# cosv-carrier-teensy40.net
KiCad netlist of a schematic drawn in EAGLE
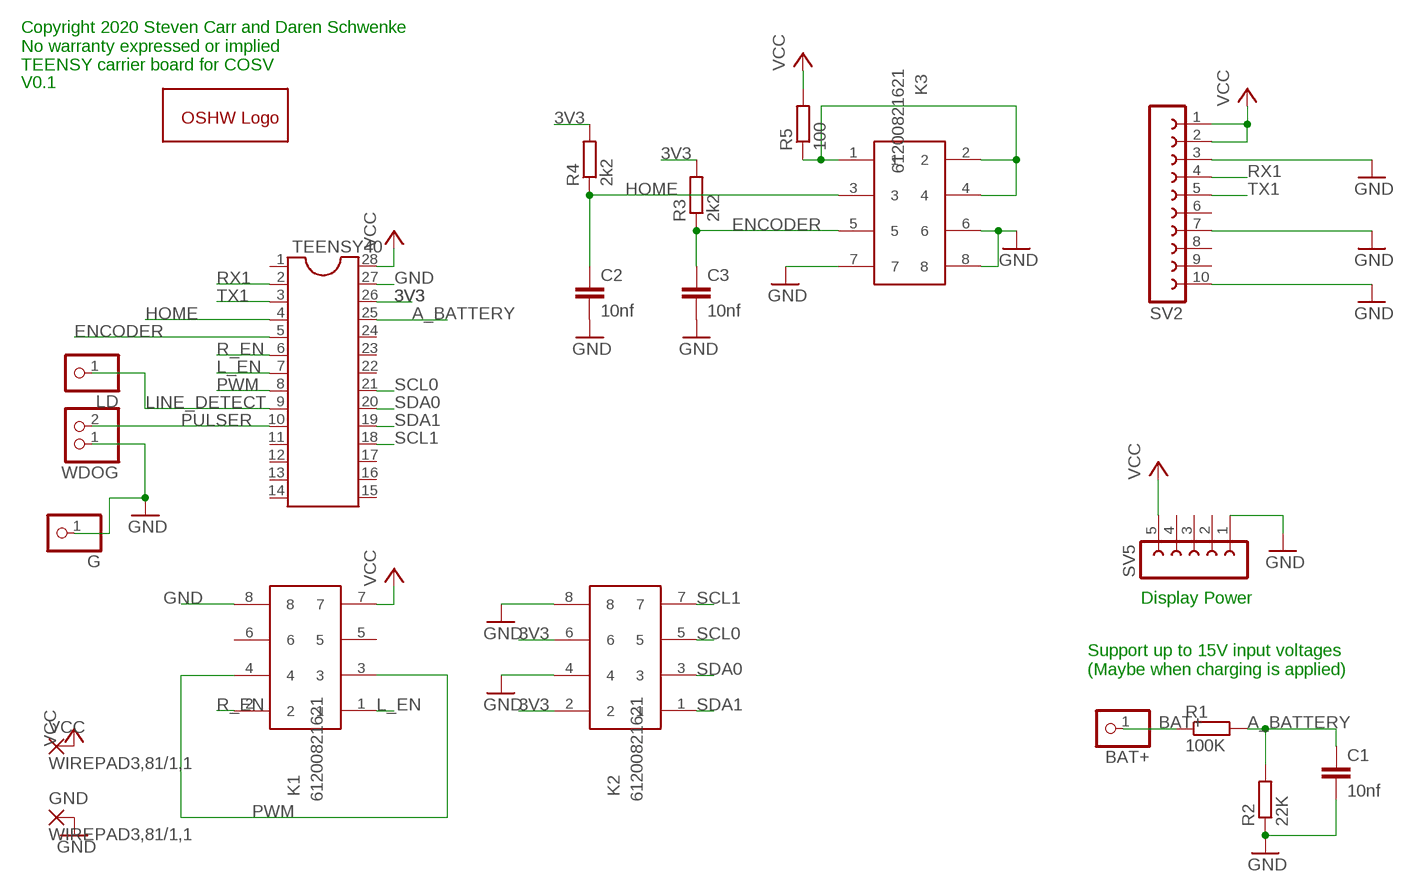
[diagram p0: schematic, sheet 1]

(export (version "E")
  (design (tool "Eeschema 10.0.6"))
  (components
    (comp (ref "BAT+")
      (value "PINHD-1X01_2.54-S")
      (footprint "eagle-import:1X01-S")
      (libsource (lib "eagle-import") (part "PINHD-1X01_2.54-S"))
    )
    (comp (ref "C1")
      (value "10nf")
      (footprint "eagle-import:C1206")
      (libsource (lib "eagle-import") (part "C-EUC1206"))
    )
    (comp (ref "C2")
      (value "10nf")
      (footprint "eagle-import:C1206")
      (libsource (lib "eagle-import") (part "C-EUC1206"))
    )
    (comp (ref "C3")
      (value "10nf")
      (footprint "eagle-import:C1206")
      (libsource (lib "eagle-import") (part "C-EUC1206"))
    )
    (comp (ref "G")
      (value "PINHD-1X01_2.54-S")
      (footprint "eagle-import:1X01-S")
      (libsource (lib "eagle-import") (part "PINHD-1X01_2.54-S"))
    )
    (comp (ref "GND")
      (value "WIREPAD3,81/1,1")
      (footprint "eagle-import:3,81_1,1")
      (libsource (lib "eagle-import") (part "WIREPAD3,81/1,1"))
    )
    (comp (ref "GOLD_ORB_SM1")
      (value "OSHWLOGOLOGO8MM")
      (footprint "eagle-import:OSHW_8MM")
      (libsource (lib "eagle-import") (part "OSHWLOGOLOGO8MM"))
    )
    (comp (ref "K1")
      (value "61200821621")
      (footprint "eagle-import:61200821621")
      (libsource (lib "eagle-import") (part "61200821621"))
    )
    (comp (ref "K2")
      (value "61200821621")
      (footprint "eagle-import:61200821621")
      (libsource (lib "eagle-import") (part "61200821621"))
    )
    (comp (ref "K3")
      (value "61200821621")
      (footprint "eagle-import:61200821621")
      (libsource (lib "eagle-import") (part "61200821621"))
    )
    (comp (ref "LD")
      (value "PINHD-1X01_2.54-S")
      (footprint "eagle-import:1X01-S")
      (libsource (lib "eagle-import") (part "PINHD-1X01_2.54-S"))
    )
    (comp (ref "R1")
      (value "100K")
      (footprint "eagle-import:R1206")
      (libsource (lib "eagle-import") (part "R-EU_R1206"))
    )
    (comp (ref "R2")
      (value "22K")
      (footprint "eagle-import:R1206")
      (libsource (lib "eagle-import") (part "R-EU_R1206"))
    )
    (comp (ref "R3")
      (value "2k2")
      (footprint "eagle-import:R1206")
      (libsource (lib "eagle-import") (part "R-EU_R1206"))
    )
    (comp (ref "R4")
      (value "2k2")
      (footprint "eagle-import:R1206")
      (libsource (lib "eagle-import") (part "R-EU_R1206"))
    )
    (comp (ref "R5")
      (value "100")
      (footprint "eagle-import:R1206")
      (libsource (lib "eagle-import") (part "R-EU_R1206"))
    )
    (comp (ref "SV2")
      (value "FE10-1")
      (footprint "eagle-import:FE10")
      (libsource (lib "eagle-import") (part "FE10-1"))
    )
    (comp (ref "SV5")
      (value "FE05W")
      (footprint "eagle-import:FE05W")
      (libsource (lib "eagle-import") (part "FE05W"))
    )
    (comp (ref "TEENSY40")
      (value "DIL28")
      (footprint "eagle-import:DIL28-6")
      (libsource (lib "eagle-import") (part "DIL28"))
    )
    (comp (ref "VCC")
      (value "WIREPAD3,81/1,1")
      (footprint "eagle-import:3,81_1,1")
      (libsource (lib "eagle-import") (part "WIREPAD3,81/1,1"))
    )
    (comp (ref "WDOG")
      (value "PINHD-1X2")
      (footprint "eagle-import:1X02")
      (libsource (lib "eagle-import") (part "PINHD-1X2"))
    )
  )
  (nets
    (net (code "1") (name "/3V3") (class "Default")
      (node (ref "K2") (pin "2") (pinfunction "2_2") (pintype "passive"))
      (node (ref "K2") (pin "6") (pinfunction "6_6") (pintype "passive"))
      (node (ref "R3") (pin "2") (pinfunction "2_2") (pintype "passive"))
      (node (ref "R4") (pin "2") (pinfunction "2_2") (pintype "passive"))
      (node (ref "TEENSY40") (pin "26") (pinfunction "26_26") (pintype "passive"))
    )
    (net (code "2") (name "/A_BATTERY") (class "Default")
      (node (ref "C1") (pin "1") (pinfunction "1_1") (pintype "passive"))
      (node (ref "R1") (pin "2") (pinfunction "2_2") (pintype "passive"))
      (node (ref "R2") (pin "2") (pinfunction "2_2") (pintype "passive"))
      (node (ref "TEENSY40") (pin "25") (pinfunction "25_25") (pintype "passive"))
    )
    (net (code "3") (name "/BAT+") (class "Default")
      (node (ref "BAT+") (pin "1") (pinfunction "1_1") (pintype "passive"))
      (node (ref "R1") (pin "1") (pinfunction "1_1") (pintype "passive"))
    )
    (net (code "4") (name "/ENCODER") (class "Default")
      (node (ref "C3") (pin "1") (pinfunction "1_1") (pintype "passive"))
      (node (ref "K3") (pin "5") (pinfunction "5_5") (pintype "passive"))
      (node (ref "R3") (pin "1") (pinfunction "1_1") (pintype "passive"))
      (node (ref "TEENSY40") (pin "5") (pinfunction "5_5") (pintype "passive"))
    )
    (net (code "5") (name "/HOME") (class "Default")
      (node (ref "C2") (pin "1") (pinfunction "1_1") (pintype "passive"))
      (node (ref "K3") (pin "3") (pinfunction "3_3") (pintype "passive"))
      (node (ref "R4") (pin "1") (pinfunction "1_1") (pintype "passive"))
      (node (ref "TEENSY40") (pin "4") (pinfunction "4_4") (pintype "passive"))
    )
    (net (code "6") (name "/LINE_DETECT") (class "Default")
      (node (ref "LD") (pin "1") (pinfunction "1_1") (pintype "passive"))
      (node (ref "TEENSY40") (pin "9") (pinfunction "9_9") (pintype "passive"))
    )
    (net (code "7") (name "/L_EN") (class "Default")
      (node (ref "K1") (pin "1") (pinfunction "1_1") (pintype "passive"))
      (node (ref "TEENSY40") (pin "7") (pinfunction "7_7") (pintype "passive"))
    )
    (net (code "8") (name "/PULSER") (class "Default")
      (node (ref "TEENSY40") (pin "10") (pinfunction "10_10") (pintype "passive"))
      (node (ref "WDOG") (pin "2") (pinfunction "2_2") (pintype "passive"))
    )
    (net (code "9") (name "/PWM") (class "Default")
      (node (ref "K1") (pin "3") (pinfunction "3_3") (pintype "passive"))
      (node (ref "K1") (pin "4") (pinfunction "4_4") (pintype "passive"))
      (node (ref "TEENSY40") (pin "8") (pinfunction "8_8") (pintype "passive"))
    )
    (net (code "10") (name "/RX1") (class "Default")
      (node (ref "SV2") (pin "4") (pinfunction "4_4") (pintype "passive"))
      (node (ref "TEENSY40") (pin "2") (pinfunction "2_2") (pintype "passive"))
    )
    (net (code "11") (name "/R_EN") (class "Default")
      (node (ref "K1") (pin "2") (pinfunction "2_2") (pintype "passive"))
      (node (ref "TEENSY40") (pin "6") (pinfunction "6_6") (pintype "passive"))
    )
    (net (code "12") (name "/SCL0") (class "Default")
      (node (ref "K2") (pin "5") (pinfunction "5_5") (pintype "passive"))
      (node (ref "TEENSY40") (pin "21") (pinfunction "21_21") (pintype "passive"))
    )
    (net (code "13") (name "/SCL1") (class "Default")
      (node (ref "K2") (pin "7") (pinfunction "7_7") (pintype "passive"))
      (node (ref "TEENSY40") (pin "18") (pinfunction "18_18") (pintype "passive"))
    )
    (net (code "14") (name "/SDA0") (class "Default")
      (node (ref "K2") (pin "3") (pinfunction "3_3") (pintype "passive"))
      (node (ref "TEENSY40") (pin "20") (pinfunction "20_20") (pintype "passive"))
    )
    (net (code "15") (name "/SDA1") (class "Default")
      (node (ref "K2") (pin "1") (pinfunction "1_1") (pintype "passive"))
      (node (ref "TEENSY40") (pin "19") (pinfunction "19_19") (pintype "passive"))
    )
    (net (code "16") (name "/TX1") (class "Default")
      (node (ref "SV2") (pin "5") (pinfunction "5_5") (pintype "passive"))
      (node (ref "TEENSY40") (pin "3") (pinfunction "3_3") (pintype "passive"))
    )
    (net (code "17") (name "GND") (class "Default")
      (node (ref "C1") (pin "2") (pinfunction "2_2") (pintype "passive"))
      (node (ref "C2") (pin "2") (pinfunction "2_2") (pintype "passive"))
      (node (ref "C3") (pin "2") (pinfunction "2_2") (pintype "passive"))
      (node (ref "G") (pin "1") (pinfunction "1_1") (pintype "passive"))
      (node (ref "GND") (pin "1") (pinfunction "P_1") (pintype "passive"))
      (node (ref "K1") (pin "8") (pinfunction "8_8") (pintype "passive"))
      (node (ref "K2") (pin "4") (pinfunction "4_4") (pintype "passive"))
      (node (ref "K2") (pin "8") (pinfunction "8_8") (pintype "passive"))
      (node (ref "K3") (pin "6") (pinfunction "6_6") (pintype "passive"))
      (node (ref "K3") (pin "7") (pinfunction "7_7") (pintype "passive"))
      (node (ref "K3") (pin "8") (pinfunction "8_8") (pintype "passive"))
      (node (ref "R2") (pin "1") (pinfunction "1_1") (pintype "passive"))
      (node (ref "SV2") (pin "10") (pinfunction "10_10") (pintype "passive"))
      (node (ref "SV2") (pin "3") (pinfunction "3_3") (pintype "passive"))
      (node (ref "SV2") (pin "7") (pinfunction "7_7") (pintype "passive"))
      (node (ref "SV5") (pin "1") (pinfunction "1_1") (pintype "passive"))
      (node (ref "TEENSY40") (pin "27") (pinfunction "27_27") (pintype "passive"))
      (node (ref "WDOG") (pin "1") (pinfunction "1_1") (pintype "passive"))
    )
    (net (code "18") (name "Net-(K3-Pad1)") (class "Default")
      (node (ref "K3") (pin "1") (pinfunction "1_1") (pintype "passive"))
      (node (ref "K3") (pin "2") (pinfunction "2_2") (pintype "passive"))
      (node (ref "K3") (pin "4") (pinfunction "4_4") (pintype "passive"))
      (node (ref "R5") (pin "1") (pinfunction "1_1") (pintype "passive"))
    )
    (net (code "19") (name "VCC") (class "Default")
      (node (ref "K1") (pin "7") (pinfunction "7_7") (pintype "passive"))
      (node (ref "R5") (pin "2") (pinfunction "2_2") (pintype "passive"))
      (node (ref "SV2") (pin "1") (pinfunction "1_1") (pintype "passive"))
      (node (ref "SV2") (pin "2") (pinfunction "2_2") (pintype "passive"))
      (node (ref "SV5") (pin "5") (pinfunction "5_5") (pintype "passive"))
      (node (ref "TEENSY40") (pin "28") (pinfunction "28_28") (pintype "passive"))
      (node (ref "VCC") (pin "1") (pinfunction "P_1") (pintype "passive"))
    )
    (net (code "20") (name "unconnected-(K1-Pad5)") (class "Default")
      (node (ref "K1") (pin "5") (pinfunction "5_5") (pintype "passive"))
    )
    (net (code "21") (name "unconnected-(K1-Pad6)") (class "Default")
      (node (ref "K1") (pin "6") (pinfunction "6_6") (pintype "passive"))
    )
    (net (code "22") (name "unconnected-(SV2-Pad6)") (class "Default")
      (node (ref "SV2") (pin "6") (pinfunction "6_6") (pintype "passive"))
    )
    (net (code "23") (name "unconnected-(SV2-Pad8)") (class "Default")
      (node (ref "SV2") (pin "8") (pinfunction "8_8") (pintype "passive"))
    )
    (net (code "24") (name "unconnected-(SV2-Pad9)") (class "Default")
      (node (ref "SV2") (pin "9") (pinfunction "9_9") (pintype "passive"))
    )
    (net (code "25") (name "unconnected-(SV5-Pad2)") (class "Default")
      (node (ref "SV5") (pin "2") (pinfunction "2_2") (pintype "passive"))
    )
    (net (code "26") (name "unconnected-(SV5-Pad3)") (class "Default")
      (node (ref "SV5") (pin "3") (pinfunction "3_3") (pintype "passive"))
    )
    (net (code "27") (name "unconnected-(SV5-Pad4)") (class "Default")
      (node (ref "SV5") (pin "4") (pinfunction "4_4") (pintype "passive"))
    )
    (net (code "28") (name "unconnected-(TEENSY40-Pad1)") (class "Default")
      (node (ref "TEENSY40") (pin "1") (pinfunction "1_1") (pintype "passive"))
    )
    (net (code "29") (name "unconnected-(TEENSY40-Pad11)") (class "Default")
      (node (ref "TEENSY40") (pin "11") (pinfunction "11_11") (pintype "passive"))
    )
    (net (code "30") (name "unconnected-(TEENSY40-Pad12)") (class "Default")
      (node (ref "TEENSY40") (pin "12") (pinfunction "12_12") (pintype "passive"))
    )
    (net (code "31") (name "unconnected-(TEENSY40-Pad13)") (class "Default")
      (node (ref "TEENSY40") (pin "13") (pinfunction "13_13") (pintype "passive"))
    )
    (net (code "32") (name "unconnected-(TEENSY40-Pad14)") (class "Default")
      (node (ref "TEENSY40") (pin "14") (pinfunction "14_14") (pintype "passive"))
    )
    (net (code "33") (name "unconnected-(TEENSY40-Pad15)") (class "Default")
      (node (ref "TEENSY40") (pin "15") (pinfunction "15_15") (pintype "passive"))
    )
    (net (code "34") (name "unconnected-(TEENSY40-Pad16)") (class "Default")
      (node (ref "TEENSY40") (pin "16") (pinfunction "16_16") (pintype "passive"))
    )
    (net (code "35") (name "unconnected-(TEENSY40-Pad17)") (class "Default")
      (node (ref "TEENSY40") (pin "17") (pinfunction "17_17") (pintype "passive"))
    )
    (net (code "36") (name "unconnected-(TEENSY40-Pad22)") (class "Default")
      (node (ref "TEENSY40") (pin "22") (pinfunction "22_22") (pintype "passive"))
    )
    (net (code "37") (name "unconnected-(TEENSY40-Pad23)") (class "Default")
      (node (ref "TEENSY40") (pin "23") (pinfunction "23_23") (pintype "passive"))
    )
    (net (code "38") (name "unconnected-(TEENSY40-Pad24)") (class "Default")
      (node (ref "TEENSY40") (pin "24") (pinfunction "24_24") (pintype "passive"))
    )
  )
)
